# IDEAL_DIODE_1.net
KiCad netlist of a schematic drawn in Altium Designer
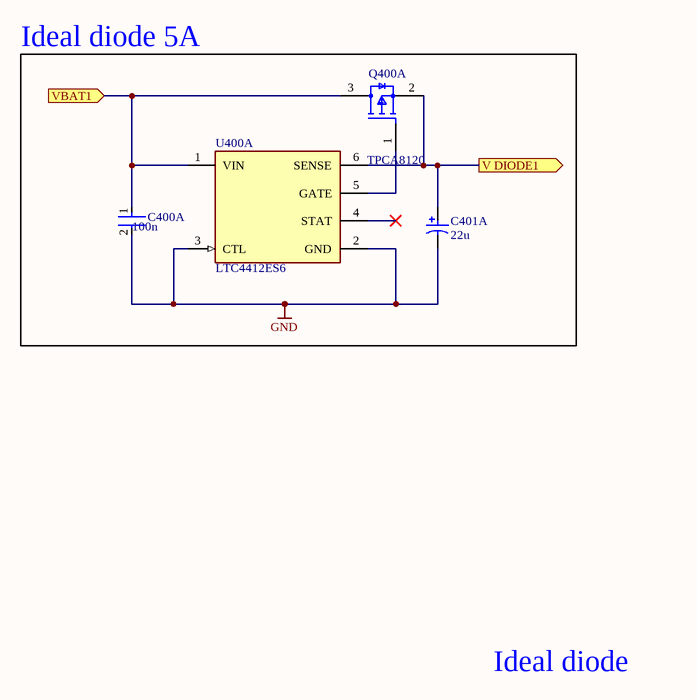
[diagram p0: IDEAL_DIODE_1.SchDoc]

(export (version "E")
  (design (tool "Eeschema 10.0.6"))
  (components
    (comp (ref "C400A")
      (value "100n")
      (footprint "FP-0603-L_1_6_0_15-W_0_81-IPC_A")
      (description "Automotive Ceramic Capacitor, 0603, 100nF, 10%, X7R, 15%, 50V")
      (fields (field (name "VOLTAGE") "50V") (field (name "TOLERANCE") "10%"))
      (libsource (lib "Altium Content Vault") (part "02cd4be3c70576c341d710602a673aa"))
    )
    (comp (ref "C401A")
      (value "22u")
      (footprint "KEMT-T491-B_L")
      (description "Tantalum Capacitor, 22 uF, +/- 10%, 10 V, -55 to 125 degC, 2-Pin SMD, RoHS, Tape and Reel")
      (fields (field (name "VOLTAGE") "10VDC") (field (name "MANUFACTURER") "Kemet"))
      (libsource (lib "Altium Content Vault") (part "CAP-P-2"))
    )
    (comp (ref "Q400A")
      (value "TPCA8120")
      (footprint "FP-527AG-MFG")
      (description "MOSFET P-CH 20V 2A SSOT3")
      (libsource (lib "Altium Content Vault") (part "d23f43cc42f60b967b7caccf14518fd"))
    )
    (comp (ref "U400A")
      (value "LTC4412ES6")
      (footprint "FP-S6-6-05-08-1636-IPC_C")
      (description "IC OR CTRLR SRC SELECT TSOT23-6")
      (libsource (lib "Altium Content Vault") (part "07cb0f4431a3a7488227ca1baae77bb"))
    )
  )
  (nets
    (net (code "1") (name "/V DIODE1") (class "Default")
      (node (ref "C401A") (pin "1") (pinfunction "1_1") (pintype "passive"))
      (node (ref "Q400A") (pin "2") (pinfunction "S_2") (pintype "passive"))
      (node (ref "U400A") (pin "6") (pinfunction "SENSE_6") (pintype "passive"))
    )
    (net (code "2") (name "/VBAT1") (class "Default")
      (node (ref "C400A") (pin "1") (pinfunction "1_1") (pintype "passive"))
      (node (ref "Q400A") (pin "3") (pinfunction "D_3") (pintype "passive"))
      (node (ref "U400A") (pin "1") (pinfunction "VIN_1") (pintype "power_in"))
    )
    (net (code "3") (name "GND") (class "Default")
      (node (ref "C400A") (pin "2") (pinfunction "2_2") (pintype "passive"))
      (node (ref "C401A") (pin "2") (pinfunction "2_2") (pintype "passive"))
      (node (ref "U400A") (pin "2") (pinfunction "GND_2") (pintype "power_in"))
      (node (ref "U400A") (pin "3") (pinfunction "CTL_3") (pintype "input"))
    )
    (net (code "4") (name "Net-(Q400A-G)") (class "Default")
      (node (ref "Q400A") (pin "1") (pinfunction "G_1") (pintype "passive"))
      (node (ref "U400A") (pin "5") (pinfunction "GATE_5") (pintype "passive"))
    )
    (net (code "5") (name "unconnected-(U400A-STAT-Pad4)") (class "Default")
      (node (ref "U400A") (pin "4") (pinfunction "STAT_4") (pintype "open_collector+no_connect"))
    )
  )
)
